# UWED.net
KiCad netlist of a schematic drawn in EAGLE
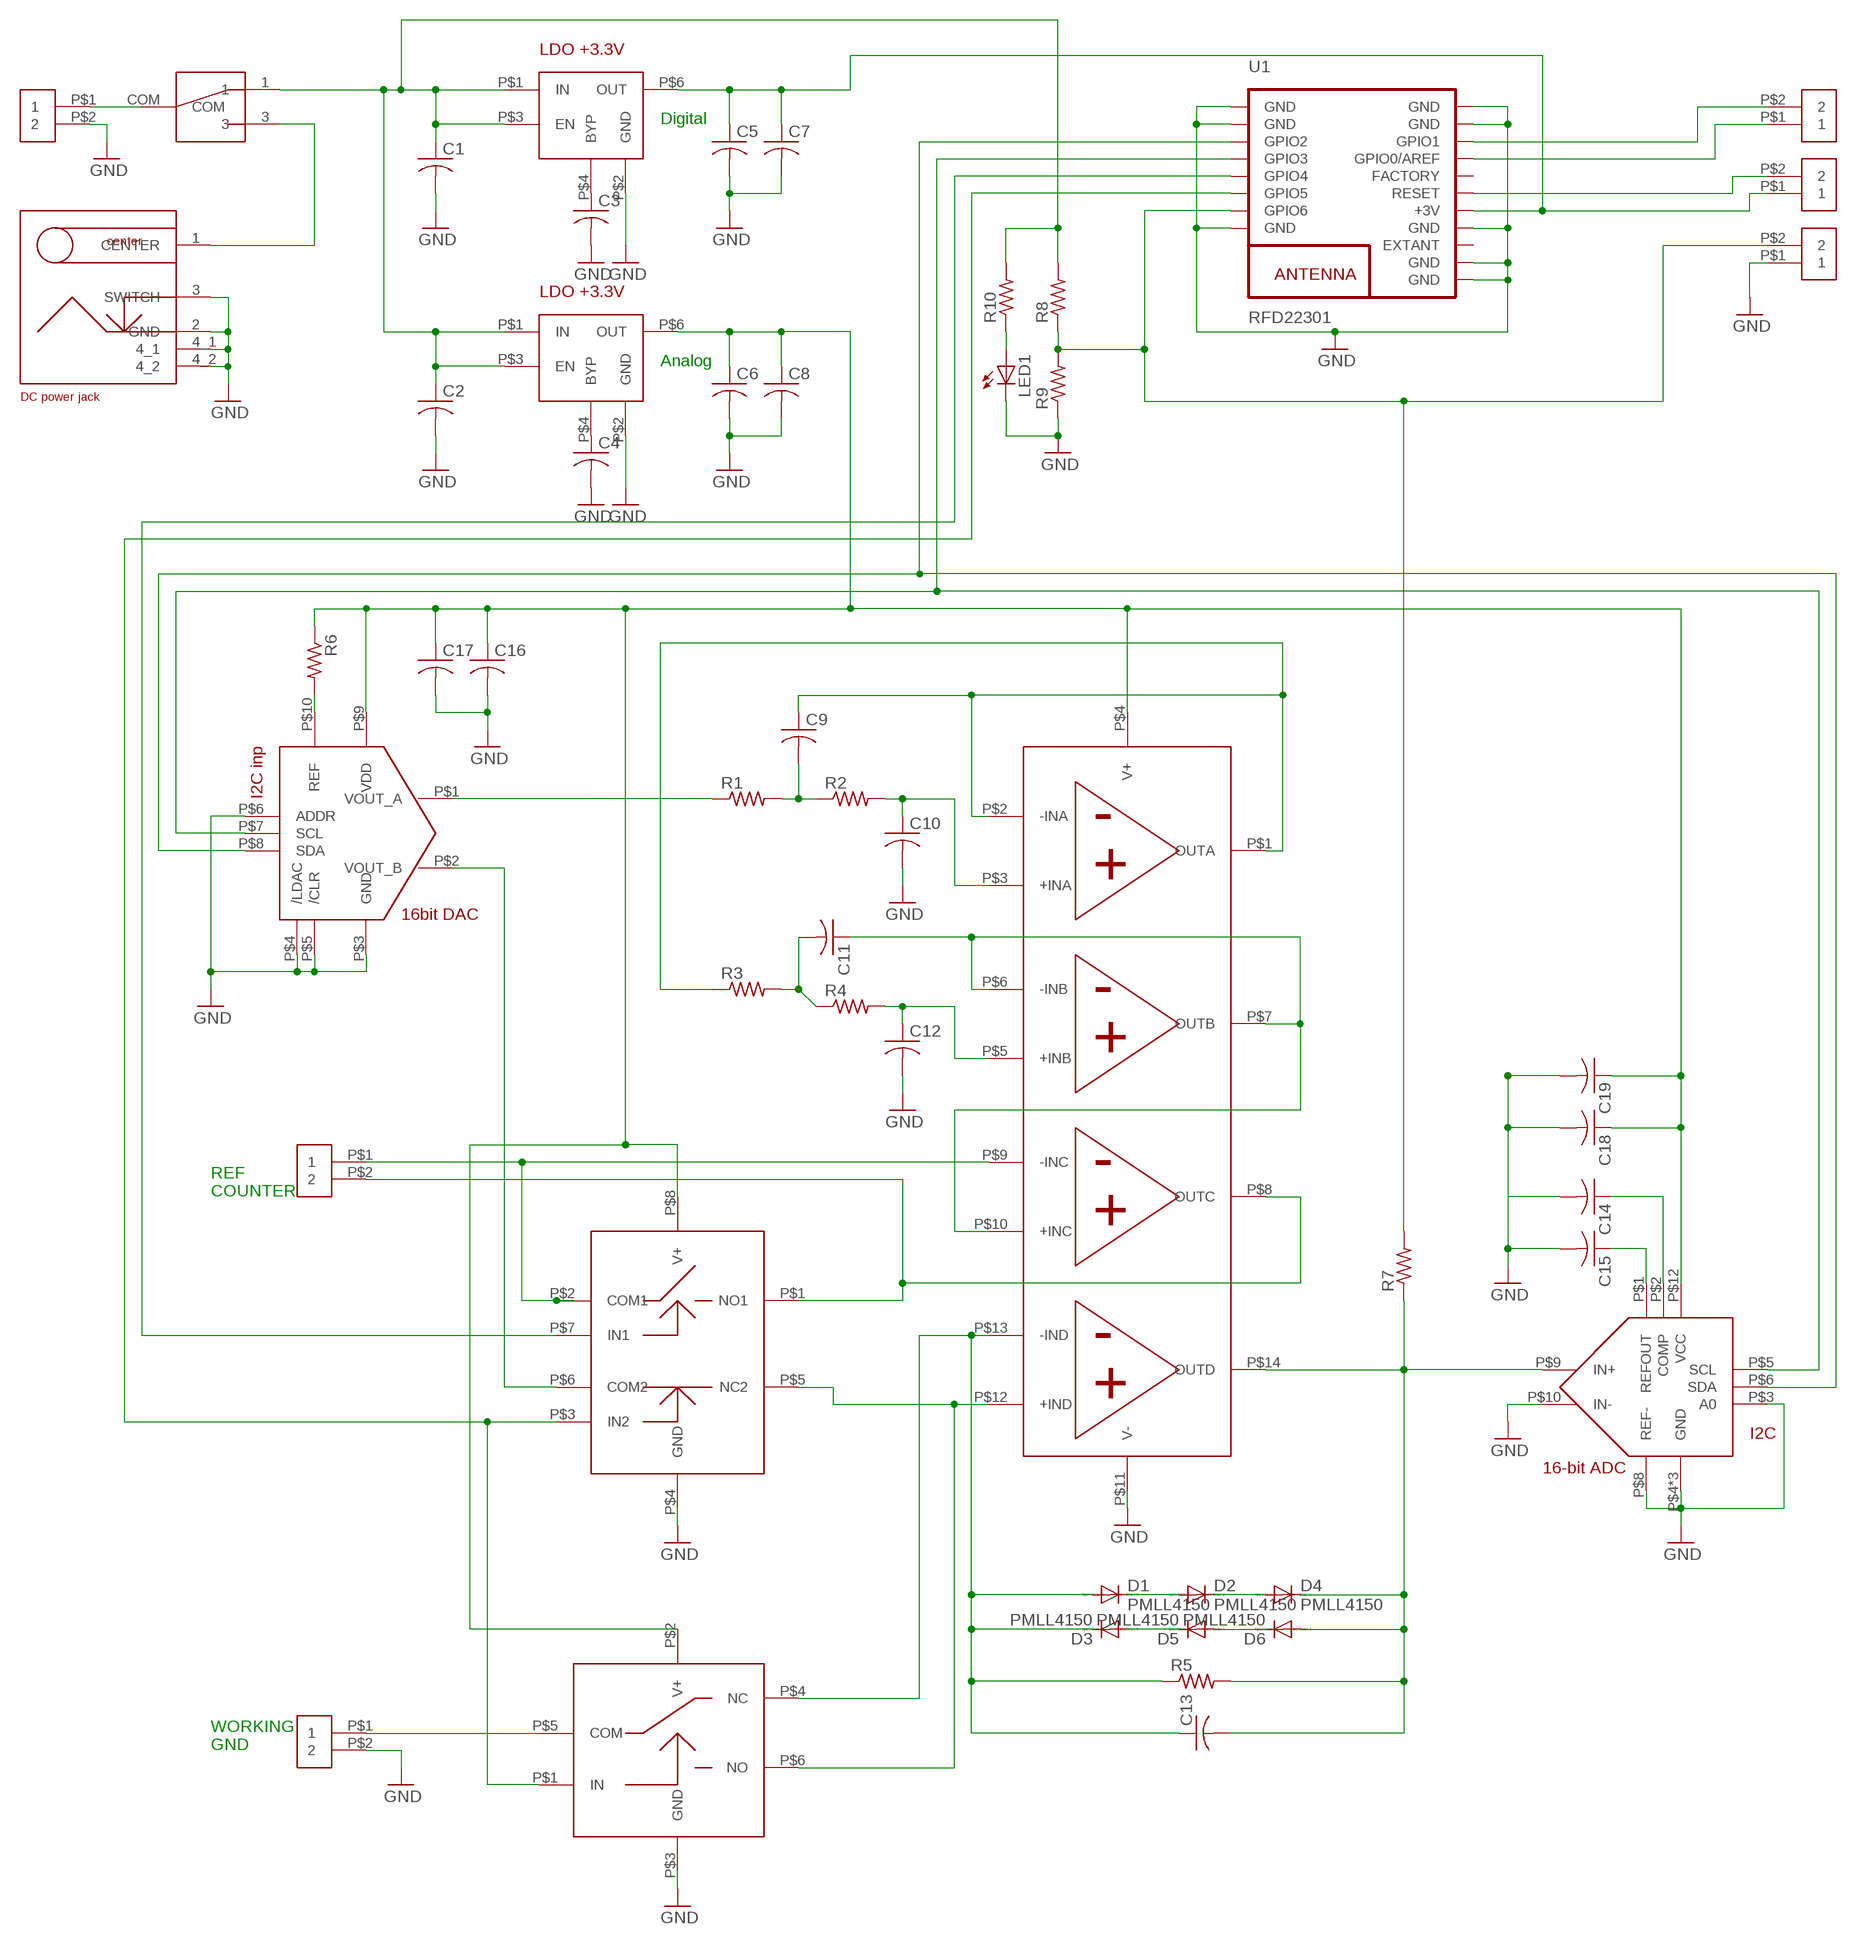
[diagram p0: schematic, sheet 1]

(export (version "E")
  (design (tool "Eeschema 10.0.6"))
  (components
    (comp (ref "C1")
      (value "C-USC0805")
      (footprint "eagle-import:C0805")
      (libsource (lib "eagle-import") (part "C-USC0805"))
    )
    (comp (ref "C2")
      (value "C-USC0805")
      (footprint "eagle-import:C0805")
      (libsource (lib "eagle-import") (part "C-USC0805"))
    )
    (comp (ref "C3")
      (value "C-USC0805")
      (footprint "eagle-import:C0805")
      (libsource (lib "eagle-import") (part "C-USC0805"))
    )
    (comp (ref "C4")
      (value "C-USC0805")
      (footprint "eagle-import:C0805")
      (libsource (lib "eagle-import") (part "C-USC0805"))
    )
    (comp (ref "C5")
      (value "C-USC0805")
      (footprint "eagle-import:C0805")
      (libsource (lib "eagle-import") (part "C-USC0805"))
    )
    (comp (ref "C6")
      (value "C-USC0805")
      (footprint "eagle-import:C0805")
      (libsource (lib "eagle-import") (part "C-USC0805"))
    )
    (comp (ref "C7")
      (value "C-USC0805")
      (footprint "eagle-import:C0805")
      (libsource (lib "eagle-import") (part "C-USC0805"))
    )
    (comp (ref "C8")
      (value "C-USC0805")
      (footprint "eagle-import:C0805")
      (libsource (lib "eagle-import") (part "C-USC0805"))
    )
    (comp (ref "C9")
      (value "C-USC0805")
      (footprint "eagle-import:C0805")
      (libsource (lib "eagle-import") (part "C-USC0805"))
    )
    (comp (ref "C10")
      (value "C-USC0805")
      (footprint "eagle-import:C0805")
      (libsource (lib "eagle-import") (part "C-USC0805"))
    )
    (comp (ref "C11")
      (value "C-USC0805")
      (footprint "eagle-import:C0805")
      (libsource (lib "eagle-import") (part "C-USC0805"))
    )
    (comp (ref "C12")
      (value "C-USC0805")
      (footprint "eagle-import:C0805")
      (libsource (lib "eagle-import") (part "C-USC0805"))
    )
    (comp (ref "C13")
      (value "C-USC0805")
      (footprint "eagle-import:C0805")
      (libsource (lib "eagle-import") (part "C-USC0805"))
    )
    (comp (ref "C14")
      (value "C-USC0805")
      (footprint "eagle-import:C0805")
      (libsource (lib "eagle-import") (part "C-USC0805"))
    )
    (comp (ref "C15")
      (value "C-USC0805")
      (footprint "eagle-import:C0805")
      (libsource (lib "eagle-import") (part "C-USC0805"))
    )
    (comp (ref "C16")
      (value "C-USC0805")
      (footprint "eagle-import:C0805")
      (libsource (lib "eagle-import") (part "C-USC0805"))
    )
    (comp (ref "C17")
      (value "C-USC0805")
      (footprint "eagle-import:C0805")
      (libsource (lib "eagle-import") (part "C-USC0805"))
    )
    (comp (ref "C18")
      (value "C-USC0805")
      (footprint "eagle-import:C0805")
      (libsource (lib "eagle-import") (part "C-USC0805"))
    )
    (comp (ref "C19")
      (value "C-USC0805")
      (footprint "eagle-import:C0805")
      (libsource (lib "eagle-import") (part "C-USC0805"))
    )
    (comp (ref "D1")
      (value "PMLL4150")
      (footprint "eagle-import:SOD80C")
      (libsource (lib "eagle-import") (part "PMLL4150"))
    )
    (comp (ref "D2")
      (value "PMLL4150")
      (footprint "eagle-import:SOD80C")
      (libsource (lib "eagle-import") (part "PMLL4150"))
    )
    (comp (ref "D3")
      (value "PMLL4150")
      (footprint "eagle-import:SOD80C")
      (libsource (lib "eagle-import") (part "PMLL4150"))
    )
    (comp (ref "D4")
      (value "PMLL4150")
      (footprint "eagle-import:SOD80C")
      (libsource (lib "eagle-import") (part "PMLL4150"))
    )
    (comp (ref "D5")
      (value "PMLL4150")
      (footprint "eagle-import:SOD80C")
      (libsource (lib "eagle-import") (part "PMLL4150"))
    )
    (comp (ref "D6")
      (value "PMLL4150")
      (footprint "eagle-import:SOD80C")
      (libsource (lib "eagle-import") (part "PMLL4150"))
    )
    (comp (ref "LED1")
      (value "LEDSML0805")
      (footprint "eagle-import:SML0805")
      (libsource (lib "eagle-import") (part "LEDSML0805"))
    )
    (comp (ref "R1")
      (value "R-US_R0805")
      (footprint "eagle-import:R0805")
      (libsource (lib "eagle-import") (part "R-US_R0805"))
    )
    (comp (ref "R2")
      (value "R-US_R0805")
      (footprint "eagle-import:R0805")
      (libsource (lib "eagle-import") (part "R-US_R0805"))
    )
    (comp (ref "R3")
      (value "R-US_R0805")
      (footprint "eagle-import:R0805")
      (libsource (lib "eagle-import") (part "R-US_R0805"))
    )
    (comp (ref "R4")
      (value "R-US_R0805")
      (footprint "eagle-import:R0805")
      (libsource (lib "eagle-import") (part "R-US_R0805"))
    )
    (comp (ref "R5")
      (value "R-US_R0805")
      (footprint "eagle-import:R0805")
      (libsource (lib "eagle-import") (part "R-US_R0805"))
    )
    (comp (ref "R6")
      (value "R-US_R0805")
      (footprint "eagle-import:R0805")
      (libsource (lib "eagle-import") (part "R-US_R0805"))
    )
    (comp (ref "R7")
      (value "R-US_R0805")
      (footprint "eagle-import:R0805")
      (libsource (lib "eagle-import") (part "R-US_R0805"))
    )
    (comp (ref "R8")
      (value "R-US_R0805")
      (footprint "eagle-import:R0805")
      (libsource (lib "eagle-import") (part "R-US_R0805"))
    )
    (comp (ref "R9")
      (value "R-US_R0805")
      (footprint "eagle-import:R0805")
      (libsource (lib "eagle-import") (part "R-US_R0805"))
    )
    (comp (ref "R10")
      (value "R-US_R0805")
      (footprint "eagle-import:R0805")
      (libsource (lib "eagle-import") (part "R-US_R0805"))
    )
    (comp (ref "U$1")
      (value "4OPAMPS-AD8608ARUZ")
      (footprint "eagle-import:MSOP14_0.65MM")
      (libsource (lib "eagle-import") (part "4OPAMPS-AD8608ARUZ"))
    )
    (comp (ref "U$2")
      (value "ADC_LTC2471IMS")
      (footprint "eagle-import:MSOP12_0.65MM")
      (libsource (lib "eagle-import") (part "ADC_LTC2471IMS"))
    )
    (comp (ref "U$3")
      (value "CONTACT_PADS_SMD_2")
      (footprint "eagle-import:CONTACT_PADS_SMD_2")
      (libsource (lib "eagle-import") (part "CONTACT_PADS_SMD_2"))
    )
    (comp (ref "U$4")
      (value "CONTACT_PADS_SMD_2")
      (footprint "eagle-import:CONTACT_PADS_SMD_2")
      (libsource (lib "eagle-import") (part "CONTACT_PADS_SMD_2"))
    )
    (comp (ref "U$5")
      (value "CONTACT_PADS_SMD_2")
      (footprint "eagle-import:CONTACT_PADS_SMD_2")
      (libsource (lib "eagle-import") (part "CONTACT_PADS_SMD_2"))
    )
    (comp (ref "U$6")
      (value "CONTACT_PADS_SMD_2")
      (footprint "eagle-import:CONTACT_PADS_SMD_2")
      (libsource (lib "eagle-import") (part "CONTACT_PADS_SMD_2"))
    )
    (comp (ref "U$7")
      (value "CONTACT_PADS_SMD_2")
      (footprint "eagle-import:CONTACT_PADS_SMD_2")
      (libsource (lib "eagle-import") (part "CONTACT_PADS_SMD_2"))
    )
    (comp (ref "U$8")
      (value "DAC_AD5667RBRMZ-2")
      (footprint "eagle-import:MSOP10_0.5MM")
      (libsource (lib "eagle-import") (part "DAC_AD5667RBRMZ-2"))
    )
    (comp (ref "U$9")
      (value "DC_JACK_0.7MM")
      (footprint "eagle-import:PJ-032H-SMT")
      (libsource (lib "eagle-import") (part "DC_JACK_0.7MM"))
    )
    (comp (ref "U$10")
      (value "LDO-MIC5205-3.3YM5-TR")
      (footprint "eagle-import:SOT-23-6")
      (libsource (lib "eagle-import") (part "LDO-MIC5205-3.3YM5-TR"))
    )
    (comp (ref "U$11")
      (value "LDO-MIC5205-3.3YM5-TR")
      (footprint "eagle-import:SOT-23-6")
      (libsource (lib "eagle-import") (part "LDO-MIC5205-3.3YM5-TR"))
    )
    (comp (ref "U$12")
      (value "SWITCH_MAX4643EUA")
      (footprint "eagle-import:MSOP8_0.65MM")
      (libsource (lib "eagle-import") (part "SWITCH_MAX4643EUA"))
    )
    (comp (ref "U$13")
      (value "SWITCH_MAX4644EUT")
      (footprint "eagle-import:SOT-23-6")
      (libsource (lib "eagle-import") (part "SWITCH_MAX4644EUT"))
    )
    (comp (ref "U$14")
      (value "SW_TOGGLELARGE")
      (footprint "eagle-import:TOGGLE_34E")
      (libsource (lib "eagle-import") (part "SW_TOGGLELARGE"))
    )
    (comp (ref "U$15")
      (value "CONTACT_PADS_SMD_2")
      (footprint "eagle-import:CONTACT_PADS_SMD_2")
      (libsource (lib "eagle-import") (part "CONTACT_PADS_SMD_2"))
    )
    (comp (ref "U1")
      (value "RFD22301")
      (footprint "eagle-import:RFD22301")
      (libsource (lib "eagle-import") (part "RFD22301"))
    )
  )
  (nets
    (net (code "1") (name "GND") (class "Default")
      (node (ref "C1") (pin "2") (pinfunction "2_2") (pintype "passive"))
      (node (ref "C10") (pin "2") (pinfunction "2_2") (pintype "passive"))
      (node (ref "C12") (pin "2") (pinfunction "2_2") (pintype "passive"))
      (node (ref "C14") (pin "2") (pinfunction "2_2") (pintype "passive"))
      (node (ref "C15") (pin "2") (pinfunction "2_2") (pintype "passive"))
      (node (ref "C16") (pin "2") (pinfunction "2_2") (pintype "passive"))
      (node (ref "C17") (pin "2") (pinfunction "2_2") (pintype "passive"))
      (node (ref "C18") (pin "2") (pinfunction "2_2") (pintype "passive"))
      (node (ref "C19") (pin "2") (pinfunction "2_2") (pintype "passive"))
      (node (ref "C2") (pin "2") (pinfunction "2_2") (pintype "passive"))
      (node (ref "C3") (pin "2") (pinfunction "2_2") (pintype "passive"))
      (node (ref "C4") (pin "2") (pinfunction "2_2") (pintype "passive"))
      (node (ref "C5") (pin "2") (pinfunction "2_2") (pintype "passive"))
      (node (ref "C6") (pin "2") (pinfunction "2_2") (pintype "passive"))
      (node (ref "C7") (pin "2") (pinfunction "2_2") (pintype "passive"))
      (node (ref "C8") (pin "2") (pinfunction "2_2") (pintype "passive"))
      (node (ref "LED1") (pin "C") (pinfunction "C_C") (pintype "passive"))
      (node (ref "R9") (pin "1") (pinfunction "1_1") (pintype "passive"))
      (node (ref "U$1") (pin "P$11") (pinfunction "V-_P$11") (pintype "bidirectional"))
      (node (ref "U$10") (pin "P$2") (pinfunction "GND_P$2") (pintype "bidirectional"))
      (node (ref "U$11") (pin "P$2") (pinfunction "GND_P$2") (pintype "bidirectional"))
      (node (ref "U$12") (pin "P$4") (pinfunction "GND_P$4") (pintype "bidirectional"))
      (node (ref "U$13") (pin "P$3") (pinfunction "GND_P$3") (pintype "bidirectional"))
      (node (ref "U$15") (pin "P$1") (pinfunction "1_P$1") (pintype "bidirectional"))
      (node (ref "U$2") (pin "P$10") (pinfunction "IN-_P$10") (pintype "bidirectional"))
      (node (ref "U$2") (pin "P$11") (pinfunction "GND_P$11") (pintype "bidirectional"))
      (node (ref "U$2") (pin "P$3") (pinfunction "A0_P$3") (pintype "bidirectional"))
      (node (ref "U$2") (pin "P$4") (pinfunction "GND_P$4") (pintype "bidirectional"))
      (node (ref "U$2") (pin "P$7") (pinfunction "GND_P$7") (pintype "bidirectional"))
      (node (ref "U$2") (pin "P$8") (pinfunction "REF-_P$8") (pintype "bidirectional"))
      (node (ref "U$3") (pin "P$2") (pinfunction "2_P$2") (pintype "bidirectional"))
      (node (ref "U$6") (pin "P$2") (pinfunction "2_P$2") (pintype "bidirectional"))
      (node (ref "U$8") (pin "P$3") (pinfunction "GND_P$3") (pintype "bidirectional"))
      (node (ref "U$8") (pin "P$4") (pinfunction "/LDAC_P$4") (pintype "bidirectional"))
      (node (ref "U$8") (pin "P$5") (pinfunction "/CLR_P$5") (pintype "bidirectional"))
      (node (ref "U$8") (pin "P$6") (pinfunction "ADDR_P$6") (pintype "bidirectional"))
      (node (ref "U$9") (pin "2") (pinfunction "GND_2") (pintype "bidirectional"))
      (node (ref "U$9") (pin "3") (pinfunction "SWITCH_3") (pintype "bidirectional"))
      (node (ref "U$9") (pin "4_1") (pinfunction "4_1_4_1") (pintype "bidirectional"))
      (node (ref "U$9") (pin "4_2") (pinfunction "4_2_4_2") (pintype "bidirectional"))
      (node (ref "U1") (pin "1") (pinfunction "GND_1") (pintype "power_in"))
      (node (ref "U1") (pin "10") (pinfunction "GND_10") (pintype "power_in"))
      (node (ref "U1") (pin "12") (pinfunction "GND_12") (pintype "power_in"))
      (node (ref "U1") (pin "18") (pinfunction "GND_18") (pintype "power_in"))
      (node (ref "U1") (pin "19") (pinfunction "GND_19") (pintype "power_in"))
      (node (ref "U1") (pin "2") (pinfunction "GND_2") (pintype "power_in"))
      (node (ref "U1") (pin "8") (pinfunction "GND_8") (pintype "power_in"))
      (node (ref "U1") (pin "9") (pinfunction "GND_9") (pintype "power_in"))
    )
    (net (code "2") (name "Net-(C9-Pad2)") (class "Default")
      (node (ref "C9") (pin "2") (pinfunction "2_2") (pintype "passive"))
      (node (ref "R1") (pin "2") (pinfunction "2_2") (pintype "passive"))
      (node (ref "R2") (pin "1") (pinfunction "1_1") (pintype "passive"))
    )
    (net (code "3") (name "Net-(C11-Pad2)") (class "Default")
      (node (ref "C11") (pin "2") (pinfunction "2_2") (pintype "passive"))
      (node (ref "R3") (pin "2") (pinfunction "2_2") (pintype "passive"))
      (node (ref "R4") (pin "1") (pinfunction "1_1") (pintype "passive"))
    )
    (net (code "4") (name "Net-(D1-PadC)") (class "Default")
      (node (ref "D1") (pin "C") (pinfunction "C_C") (pintype "passive"))
      (node (ref "D2") (pin "A") (pinfunction "A_A") (pintype "passive"))
    )
    (net (code "5") (name "Net-(D2-PadC)") (class "Default")
      (node (ref "D2") (pin "C") (pinfunction "C_C") (pintype "passive"))
      (node (ref "D4") (pin "A") (pinfunction "A_A") (pintype "passive"))
    )
    (net (code "6") (name "Net-(D3-PadA)") (class "Default")
      (node (ref "D3") (pin "A") (pinfunction "A_A") (pintype "passive"))
      (node (ref "D5") (pin "C") (pinfunction "C_C") (pintype "passive"))
    )
    (net (code "7") (name "Net-(D5-PadA)") (class "Default")
      (node (ref "D5") (pin "A") (pinfunction "A_A") (pintype "passive"))
      (node (ref "D6") (pin "C") (pinfunction "C_C") (pintype "passive"))
    )
    (net (code "8") (name "Net-(LED1-PadA)") (class "Default")
      (node (ref "LED1") (pin "A") (pinfunction "A_A") (pintype "passive"))
      (node (ref "R10") (pin "1") (pinfunction "1_1") (pintype "passive"))
    )
    (net (code "9") (name "Net-(U$1-+INA)") (class "Default")
      (node (ref "C10") (pin "1") (pinfunction "1_1") (pintype "passive"))
      (node (ref "R2") (pin "2") (pinfunction "2_2") (pintype "passive"))
      (node (ref "U$1") (pin "P$3") (pinfunction "+INA_P$3") (pintype "bidirectional"))
    )
    (net (code "10") (name "Net-(U$1-+INB)") (class "Default")
      (node (ref "C12") (pin "1") (pinfunction "1_1") (pintype "passive"))
      (node (ref "R4") (pin "2") (pinfunction "2_2") (pintype "passive"))
      (node (ref "U$1") (pin "P$5") (pinfunction "+INB_P$5") (pintype "bidirectional"))
    )
    (net (code "11") (name "Net-(U$1-+INC)") (class "Default")
      (node (ref "C11") (pin "1") (pinfunction "1_1") (pintype "passive"))
      (node (ref "U$1") (pin "P$10") (pinfunction "+INC_P$10") (pintype "bidirectional"))
      (node (ref "U$1") (pin "P$6") (pinfunction "-INB_P$6") (pintype "bidirectional"))
      (node (ref "U$1") (pin "P$7") (pinfunction "OUTB_P$7") (pintype "bidirectional"))
    )
    (net (code "12") (name "Net-(U$1-+IND)") (class "Default")
      (node (ref "U$1") (pin "P$12") (pinfunction "+IND_P$12") (pintype "bidirectional"))
      (node (ref "U$12") (pin "P$5") (pinfunction "NC2_P$5") (pintype "bidirectional"))
      (node (ref "U$13") (pin "P$6") (pinfunction "NO_P$6") (pintype "bidirectional"))
    )
    (net (code "13") (name "Net-(U$1--INA)") (class "Default")
      (node (ref "C9") (pin "1") (pinfunction "1_1") (pintype "passive"))
      (node (ref "R3") (pin "1") (pinfunction "1_1") (pintype "passive"))
      (node (ref "U$1") (pin "P$1") (pinfunction "OUTA_P$1") (pintype "bidirectional"))
      (node (ref "U$1") (pin "P$2") (pinfunction "-INA_P$2") (pintype "bidirectional"))
    )
    (net (code "14") (name "Net-(U$1--INC)") (class "Default")
      (node (ref "U$1") (pin "P$9") (pinfunction "-INC_P$9") (pintype "bidirectional"))
      (node (ref "U$12") (pin "P$2") (pinfunction "COM1_P$2") (pintype "bidirectional"))
      (node (ref "U$7") (pin "P$1") (pinfunction "1_P$1") (pintype "bidirectional"))
    )
    (net (code "15") (name "Net-(U$1--IND)") (class "Default")
      (node (ref "C13") (pin "1") (pinfunction "1_1") (pintype "passive"))
      (node (ref "D1") (pin "A") (pinfunction "A_A") (pintype "passive"))
      (node (ref "D3") (pin "C") (pinfunction "C_C") (pintype "passive"))
      (node (ref "R5") (pin "1") (pinfunction "1_1") (pintype "passive"))
      (node (ref "U$1") (pin "P$13") (pinfunction "-IND_P$13") (pintype "bidirectional"))
      (node (ref "U$13") (pin "P$4") (pinfunction "NC_P$4") (pintype "bidirectional"))
    )
    (net (code "16") (name "Net-(U$1-OUTC)") (class "Default")
      (node (ref "U$1") (pin "P$8") (pinfunction "OUTC_P$8") (pintype "bidirectional"))
      (node (ref "U$12") (pin "P$1") (pinfunction "NO1_P$1") (pintype "bidirectional"))
      (node (ref "U$7") (pin "P$2") (pinfunction "2_P$2") (pintype "bidirectional"))
    )
    (net (code "17") (name "Net-(U$1-OUTD)") (class "Default")
      (node (ref "C13") (pin "2") (pinfunction "2_2") (pintype "passive"))
      (node (ref "D4") (pin "C") (pinfunction "C_C") (pintype "passive"))
      (node (ref "D6") (pin "A") (pinfunction "A_A") (pintype "passive"))
      (node (ref "R5") (pin "2") (pinfunction "2_2") (pintype "passive"))
      (node (ref "R7") (pin "1") (pinfunction "1_1") (pintype "passive"))
      (node (ref "U$1") (pin "P$14") (pinfunction "OUTD_P$14") (pintype "bidirectional"))
      (node (ref "U$2") (pin "P$9") (pinfunction "IN+_P$9") (pintype "bidirectional"))
    )
    (net (code "18") (name "Net-(U$1-V+)") (class "Default")
      (node (ref "C16") (pin "1") (pinfunction "1_1") (pintype "passive"))
      (node (ref "C17") (pin "1") (pinfunction "1_1") (pintype "passive"))
      (node (ref "C18") (pin "1") (pinfunction "1_1") (pintype "passive"))
      (node (ref "C19") (pin "1") (pinfunction "1_1") (pintype "passive"))
      (node (ref "C6") (pin "1") (pinfunction "1_1") (pintype "passive"))
      (node (ref "C8") (pin "1") (pinfunction "1_1") (pintype "passive"))
      (node (ref "R6") (pin "1") (pinfunction "1_1") (pintype "passive"))
      (node (ref "U$1") (pin "P$4") (pinfunction "V+_P$4") (pintype "bidirectional"))
      (node (ref "U$11") (pin "P$6") (pinfunction "OUT_P$6") (pintype "bidirectional"))
      (node (ref "U$12") (pin "P$8") (pinfunction "V+_P$8") (pintype "bidirectional"))
      (node (ref "U$13") (pin "P$2") (pinfunction "V+_P$2") (pintype "bidirectional"))
      (node (ref "U$2") (pin "P$12") (pinfunction "VCC_P$12") (pintype "bidirectional"))
      (node (ref "U$8") (pin "P$9") (pinfunction "VDD_P$9") (pintype "bidirectional"))
    )
    (net (code "19") (name "Net-(U$2-COMP)") (class "Default")
      (node (ref "C14") (pin "1") (pinfunction "1_1") (pintype "passive"))
      (node (ref "U$2") (pin "P$2") (pinfunction "COMP_P$2") (pintype "bidirectional"))
    )
    (net (code "20") (name "Net-(U$2-REFOUT)") (class "Default")
      (node (ref "C15") (pin "1") (pinfunction "1_1") (pintype "passive"))
      (node (ref "U$2") (pin "P$1") (pinfunction "REFOUT_P$1") (pintype "bidirectional"))
    )
    (net (code "21") (name "Net-(U$2-SCL)") (class "Default")
      (node (ref "U$2") (pin "P$5") (pinfunction "SCL_P$5") (pintype "bidirectional"))
      (node (ref "U$8") (pin "P$7") (pinfunction "SCL_P$7") (pintype "bidirectional"))
      (node (ref "U1") (pin "4") (pinfunction "GPIO3_4") (pintype "bidirectional"))
    )
    (net (code "22") (name "Net-(U$2-SDA)") (class "Default")
      (node (ref "U$2") (pin "P$6") (pinfunction "SDA_P$6") (pintype "bidirectional"))
      (node (ref "U$8") (pin "P$8") (pinfunction "SDA_P$8") (pintype "bidirectional"))
      (node (ref "U1") (pin "3") (pinfunction "GPIO2_3") (pintype "bidirectional"))
    )
    (net (code "23") (name "Net-(U$3-1)") (class "Default")
      (node (ref "U$14") (pin "COM") (pinfunction "COM_COM") (pintype "bidirectional"))
      (node (ref "U$3") (pin "P$1") (pinfunction "1_P$1") (pintype "bidirectional"))
    )
    (net (code "24") (name "Net-(U$4-2)") (class "Default")
      (node (ref "U$4") (pin "P$2") (pinfunction "2_P$2") (pintype "bidirectional"))
      (node (ref "U1") (pin "14") (pinfunction "RESET_14") (pintype "bidirectional"))
    )
    (net (code "25") (name "Net-(U$5-1)") (class "Default")
      (node (ref "U$5") (pin "P$1") (pinfunction "1_P$1") (pintype "bidirectional"))
      (node (ref "U1") (pin "16") (pinfunction "GPIO0/AREF_16") (pintype "bidirectional"))
    )
    (net (code "26") (name "Net-(U$5-2)") (class "Default")
      (node (ref "U$5") (pin "P$2") (pinfunction "2_P$2") (pintype "bidirectional"))
      (node (ref "U1") (pin "17") (pinfunction "GPIO1_17") (pintype "bidirectional"))
    )
    (net (code "27") (name "Net-(U$8-REF)") (class "Default")
      (node (ref "R6") (pin "2") (pinfunction "2_2") (pintype "passive"))
      (node (ref "U$8") (pin "P$10") (pinfunction "REF_P$10") (pintype "bidirectional"))
    )
    (net (code "28") (name "Net-(U$8-VOUT_A)") (class "Default")
      (node (ref "R1") (pin "1") (pinfunction "1_1") (pintype "passive"))
      (node (ref "U$8") (pin "P$1") (pinfunction "VOUT_A_P$1") (pintype "bidirectional"))
    )
    (net (code "29") (name "Net-(U$9-CENTER)") (class "Default")
      (node (ref "U$14") (pin "3") (pinfunction "3_3") (pintype "bidirectional"))
      (node (ref "U$9") (pin "1") (pinfunction "CENTER_1") (pintype "bidirectional"))
    )
    (net (code "30") (name "Net-(U$10-BYP)") (class "Default")
      (node (ref "C3") (pin "1") (pinfunction "1_1") (pintype "passive"))
      (node (ref "U$10") (pin "P$4") (pinfunction "BYP_P$4") (pintype "bidirectional"))
    )
    (net (code "31") (name "Net-(U$10-EN)") (class "Default")
      (node (ref "C1") (pin "1") (pinfunction "1_1") (pintype "passive"))
      (node (ref "C2") (pin "1") (pinfunction "1_1") (pintype "passive"))
      (node (ref "R10") (pin "2") (pinfunction "2_2") (pintype "passive"))
      (node (ref "R8") (pin "2") (pinfunction "2_2") (pintype "passive"))
      (node (ref "U$10") (pin "P$1") (pinfunction "IN_P$1") (pintype "bidirectional"))
      (node (ref "U$10") (pin "P$3") (pinfunction "EN_P$3") (pintype "bidirectional"))
      (node (ref "U$11") (pin "P$1") (pinfunction "IN_P$1") (pintype "bidirectional"))
      (node (ref "U$11") (pin "P$3") (pinfunction "EN_P$3") (pintype "bidirectional"))
      (node (ref "U$14") (pin "1") (pinfunction "1_1") (pintype "bidirectional"))
    )
    (net (code "32") (name "Net-(U$10-OUT)") (class "Default")
      (node (ref "C5") (pin "1") (pinfunction "1_1") (pintype "passive"))
      (node (ref "C7") (pin "1") (pinfunction "1_1") (pintype "passive"))
      (node (ref "U$10") (pin "P$6") (pinfunction "OUT_P$6") (pintype "bidirectional"))
      (node (ref "U$4") (pin "P$1") (pinfunction "1_P$1") (pintype "bidirectional"))
      (node (ref "U1") (pin "13") (pinfunction "+3V_13") (pintype "power_in"))
    )
    (net (code "33") (name "Net-(U$11-BYP)") (class "Default")
      (node (ref "C4") (pin "1") (pinfunction "1_1") (pintype "passive"))
      (node (ref "U$11") (pin "P$4") (pinfunction "BYP_P$4") (pintype "bidirectional"))
    )
    (net (code "34") (name "Net-(U$12-COM2)") (class "Default")
      (node (ref "U$12") (pin "P$6") (pinfunction "COM2_P$6") (pintype "bidirectional"))
      (node (ref "U$8") (pin "P$2") (pinfunction "VOUT_B_P$2") (pintype "bidirectional"))
    )
    (net (code "35") (name "Net-(U$12-IN1)") (class "Default")
      (node (ref "U$12") (pin "P$7") (pinfunction "IN1_P$7") (pintype "bidirectional"))
      (node (ref "U1") (pin "5") (pinfunction "GPIO4_5") (pintype "bidirectional"))
    )
    (net (code "36") (name "Net-(U$12-IN2)") (class "Default")
      (node (ref "U$12") (pin "P$3") (pinfunction "IN2_P$3") (pintype "bidirectional"))
      (node (ref "U$13") (pin "P$1") (pinfunction "IN_P$1") (pintype "bidirectional"))
      (node (ref "U1") (pin "6") (pinfunction "GPIO5_6") (pintype "bidirectional"))
    )
    (net (code "37") (name "Net-(U$13-COM)") (class "Default")
      (node (ref "U$13") (pin "P$5") (pinfunction "COM_P$5") (pintype "bidirectional"))
      (node (ref "U$6") (pin "P$1") (pinfunction "1_P$1") (pintype "bidirectional"))
    )
    (net (code "38") (name "Net-(U$15-2)") (class "Default")
      (node (ref "R7") (pin "2") (pinfunction "2_2") (pintype "passive"))
      (node (ref "R8") (pin "1") (pinfunction "1_1") (pintype "passive"))
      (node (ref "R9") (pin "2") (pinfunction "2_2") (pintype "passive"))
      (node (ref "U$15") (pin "P$2") (pinfunction "2_P$2") (pintype "bidirectional"))
      (node (ref "U1") (pin "7") (pinfunction "GPIO6_7") (pintype "bidirectional"))
    )
    (net (code "39") (name "unconnected-(U1-EXTANT-Pad11)") (class "Default")
      (node (ref "U1") (pin "11") (pinfunction "EXTANT_11") (pintype "no_connect"))
    )
    (net (code "40") (name "unconnected-(U1-FACTORY-Pad15)") (class "Default")
      (node (ref "U1") (pin "15") (pinfunction "FACTORY_15") (pintype "bidirectional"))
    )
  )
)
